# MICRO_SQUARED_SENSING_WITH_DIODES.net
KiCad netlist of a schematic drawn in EAGLE
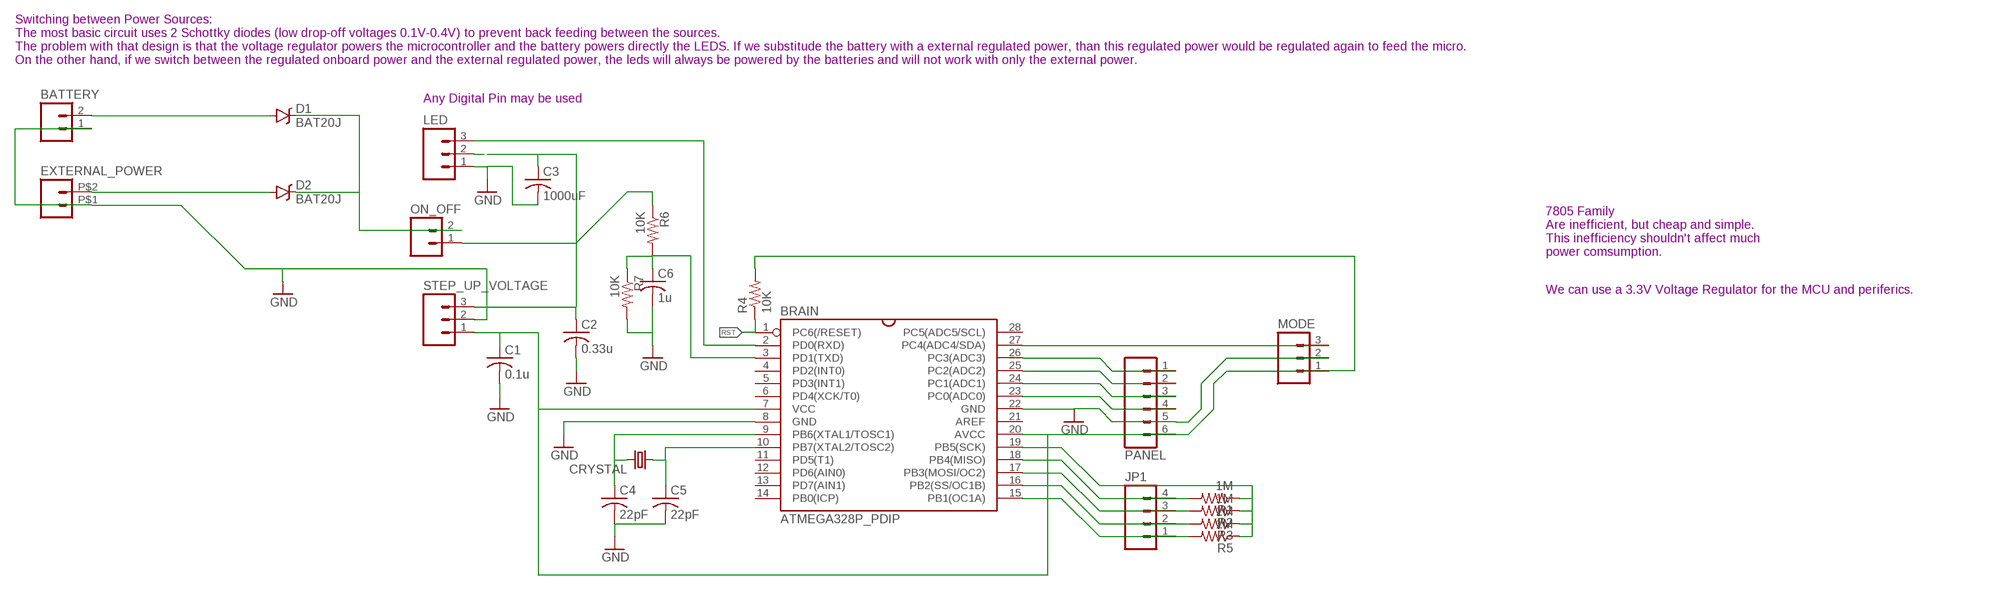
[diagram p0: schematic, sheet 1]

(export (version "E")
  (design (tool "Eeschema 10.0.6"))
  (components
    (comp (ref "BATTERY")
      (value "M02PTH")
      (footprint "eagle-import:1X02")
      (libsource (lib "eagle-import") (part "M02PTH"))
    )
    (comp (ref "BRAIN")
      (value "ATMEGA328P_PDIP")
      (footprint "eagle-import:DIL-28-3")
      (libsource (lib "eagle-import") (part "ATMEGA328P_PDIP"))
    )
    (comp (ref "C1")
      (value "0.1u")
      (footprint "eagle-import:C025-025X050")
      (libsource (lib "eagle-import") (part "C-US025-025X050"))
    )
    (comp (ref "C2")
      (value "0.33u")
      (footprint "eagle-import:C025-025X050")
      (libsource (lib "eagle-import") (part "C-US025-025X050"))
    )
    (comp (ref "C3")
      (value "1000uF")
      (footprint "eagle-import:C050-075X075")
      (libsource (lib "eagle-import") (part "C-US050-075X075"))
    )
    (comp (ref "C4")
      (value "22pF")
      (footprint "eagle-import:C025-024X044")
      (libsource (lib "eagle-import") (part "C-US025-024X044"))
    )
    (comp (ref "C5")
      (value "22pF")
      (footprint "eagle-import:C025-024X044")
      (libsource (lib "eagle-import") (part "C-US025-024X044"))
    )
    (comp (ref "C6")
      (value "1u")
      (footprint "eagle-import:C025-025X050")
      (libsource (lib "eagle-import") (part "C-US025-025X050"))
    )
    (comp (ref "CRYSTAL")
      (value "CRYSTALHC49US")
      (footprint "eagle-import:HC49US")
      (libsource (lib "eagle-import") (part "CRYSTALHC49US"))
    )
    (comp (ref "D1")
      (value "BAT20J")
      (footprint "eagle-import:SOD-323")
      (libsource (lib "eagle-import") (part "DIODE-SCHOTTKY-BAT20J"))
    )
    (comp (ref "D2")
      (value "BAT20J")
      (footprint "eagle-import:SOD-323")
      (libsource (lib "eagle-import") (part "DIODE-SCHOTTKY-BAT20J"))
    )
    (comp (ref "EXTERNAL_POWER")
      (value "M02PTH2")
      (footprint "eagle-import:1X02_BIG")
      (libsource (lib "eagle-import") (part "M02PTH2"))
    )
    (comp (ref "JP1")
      (value "M04PTH")
      (footprint "eagle-import:1X04")
      (libsource (lib "eagle-import") (part "M04PTH"))
    )
    (comp (ref "LED")
      (value "M03PTH")
      (footprint "eagle-import:1X03")
      (libsource (lib "eagle-import") (part "M03PTH"))
    )
    (comp (ref "MODE")
      (value "M03PTH")
      (footprint "eagle-import:1X03")
      (libsource (lib "eagle-import") (part "M03PTH"))
    )
    (comp (ref "ON_OFF")
      (value "M02PTH")
      (footprint "eagle-import:1X02")
      (libsource (lib "eagle-import") (part "M02PTH"))
    )
    (comp (ref "PANEL")
      (value "M06NO_SILK_FEMALE_PTH")
      (footprint "eagle-import:1X06_NO_SILK")
      (libsource (lib "eagle-import") (part "M06NO_SILK_FEMALE_PTH"))
    )
    (comp (ref "R1")
      (value "1M")
      (footprint "eagle-import:AXIAL-0.3")
      (libsource (lib "eagle-import") (part "RESISTORAXIAL-0.3"))
    )
    (comp (ref "R2")
      (value "1M")
      (footprint "eagle-import:AXIAL-0.3")
      (libsource (lib "eagle-import") (part "RESISTORAXIAL-0.3"))
    )
    (comp (ref "R3")
      (value "1M")
      (footprint "eagle-import:AXIAL-0.3")
      (libsource (lib "eagle-import") (part "RESISTORAXIAL-0.3"))
    )
    (comp (ref "R4")
      (value "10K")
      (footprint "eagle-import:AXIAL-0.3")
      (libsource (lib "eagle-import") (part "RESISTORAXIAL-0.3"))
    )
    (comp (ref "R5")
      (value "1M")
      (footprint "eagle-import:AXIAL-0.3")
      (libsource (lib "eagle-import") (part "RESISTORAXIAL-0.3"))
    )
    (comp (ref "R6")
      (value "10K")
      (footprint "eagle-import:AXIAL-0.3")
      (libsource (lib "eagle-import") (part "RESISTORAXIAL-0.3"))
    )
    (comp (ref "R7")
      (value "10K")
      (footprint "eagle-import:AXIAL-0.3")
      (libsource (lib "eagle-import") (part "RESISTORAXIAL-0.3"))
    )
    (comp (ref "STEP_UP_VOLTAGE")
      (value "M03PTH")
      (footprint "eagle-import:1X03")
      (libsource (lib "eagle-import") (part "M03PTH"))
    )
  )
  (nets
    (net (code "1") (name "GND") (class "Default")
      (node (ref "BATTERY") (pin "1") (pinfunction "1_1") (pintype "passive"))
      (node (ref "BRAIN") (pin "22") (pinfunction "GND_22") (pintype "bidirectional"))
      (node (ref "BRAIN") (pin "8") (pinfunction "GND_8") (pintype "bidirectional"))
      (node (ref "C1") (pin "2") (pinfunction "2_2") (pintype "passive"))
      (node (ref "C2") (pin "2") (pinfunction "2_2") (pintype "passive"))
      (node (ref "C3") (pin "2") (pinfunction "2_2") (pintype "passive"))
      (node (ref "C4") (pin "2") (pinfunction "2_2") (pintype "passive"))
      (node (ref "C5") (pin "2") (pinfunction "2_2") (pintype "passive"))
      (node (ref "C6") (pin "2") (pinfunction "2_2") (pintype "passive"))
      (node (ref "EXTERNAL_POWER") (pin "P$1") (pinfunction "1_P$1") (pintype "passive"))
      (node (ref "LED") (pin "1") (pinfunction "1_1") (pintype "passive"))
      (node (ref "MODE") (pin "2") (pinfunction "2_2") (pintype "passive"))
      (node (ref "PANEL") (pin "5") (pinfunction "5_5") (pintype "passive"))
      (node (ref "R7") (pin "P$2") (pinfunction "2_P$2") (pintype "passive"))
      (node (ref "STEP_UP_VOLTAGE") (pin "2") (pinfunction "2_2") (pintype "passive"))
    )
    (net (code "2") (name "Net-(BATTERY-Pad2)") (class "Default")
      (node (ref "BATTERY") (pin "2") (pinfunction "2_2") (pintype "passive"))
      (node (ref "D1") (pin "A") (pinfunction "A_A") (pintype "passive"))
    )
    (net (code "3") (name "Net-(BRAIN-AVCC)") (class "Default")
      (node (ref "BRAIN") (pin "20") (pinfunction "AVCC_20") (pintype "bidirectional"))
      (node (ref "BRAIN") (pin "7") (pinfunction "VCC_7") (pintype "bidirectional"))
      (node (ref "C1") (pin "1") (pinfunction "1_1") (pintype "passive"))
      (node (ref "MODE") (pin "1") (pinfunction "1_1") (pintype "passive"))
      (node (ref "PANEL") (pin "6") (pinfunction "6_6") (pintype "passive"))
      (node (ref "R4") (pin "P$2") (pinfunction "2_P$2") (pintype "passive"))
      (node (ref "STEP_UP_VOLTAGE") (pin "1") (pinfunction "1_1") (pintype "passive"))
    )
    (net (code "4") (name "Net-(BRAIN-PB1(OC1A))") (class "Default")
      (node (ref "BRAIN") (pin "15") (pinfunction "PB1(OC1A)_15") (pintype "bidirectional"))
      (node (ref "JP1") (pin "1") (pinfunction "1_1") (pintype "passive"))
      (node (ref "R5") (pin "P$2") (pinfunction "2_P$2") (pintype "passive"))
    )
    (net (code "5") (name "Net-(BRAIN-PB2(SS{slash}OC1B))") (class "Default")
      (node (ref "BRAIN") (pin "16") (pinfunction "PB2(SS/OC1B)_16") (pintype "bidirectional"))
      (node (ref "JP1") (pin "2") (pinfunction "2_2") (pintype "passive"))
      (node (ref "R3") (pin "P$2") (pinfunction "2_P$2") (pintype "passive"))
    )
    (net (code "6") (name "Net-(BRAIN-PB3(MOSI{slash}OC2))") (class "Default")
      (node (ref "BRAIN") (pin "17") (pinfunction "PB3(MOSI/OC2)_17") (pintype "bidirectional"))
      (node (ref "JP1") (pin "3") (pinfunction "3_3") (pintype "passive"))
      (node (ref "R2") (pin "P$2") (pinfunction "2_P$2") (pintype "passive"))
    )
    (net (code "7") (name "Net-(BRAIN-PB4(MISO))") (class "Default")
      (node (ref "BRAIN") (pin "18") (pinfunction "PB4(MISO)_18") (pintype "bidirectional"))
      (node (ref "JP1") (pin "4") (pinfunction "4_4") (pintype "passive"))
      (node (ref "R1") (pin "P$2") (pinfunction "2_P$2") (pintype "passive"))
    )
    (net (code "8") (name "Net-(BRAIN-PB5(SCK))") (class "Default")
      (node (ref "BRAIN") (pin "19") (pinfunction "PB5(SCK)_19") (pintype "bidirectional"))
      (node (ref "R1") (pin "P$1") (pinfunction "1_P$1") (pintype "passive"))
      (node (ref "R2") (pin "P$1") (pinfunction "1_P$1") (pintype "passive"))
      (node (ref "R3") (pin "P$1") (pinfunction "1_P$1") (pintype "passive"))
      (node (ref "R5") (pin "P$1") (pinfunction "1_P$1") (pintype "passive"))
    )
    (net (code "9") (name "Net-(BRAIN-PB6(XTAL1{slash}TOSC1))") (class "Default")
      (node (ref "BRAIN") (pin "9") (pinfunction "PB6(XTAL1/TOSC1)_9") (pintype "bidirectional"))
      (node (ref "C4") (pin "1") (pinfunction "1_1") (pintype "passive"))
      (node (ref "CRYSTAL") (pin "2") (pinfunction "2_2") (pintype "passive"))
    )
    (net (code "10") (name "Net-(BRAIN-PB7(XTAL2{slash}TOSC2))") (class "Default")
      (node (ref "BRAIN") (pin "10") (pinfunction "PB7(XTAL2/TOSC2)_10") (pintype "bidirectional"))
      (node (ref "C5") (pin "1") (pinfunction "1_1") (pintype "passive"))
      (node (ref "CRYSTAL") (pin "1") (pinfunction "1_1") (pintype "passive"))
    )
    (net (code "11") (name "Net-(BRAIN-PC0(ADC0))") (class "Default")
      (node (ref "BRAIN") (pin "23") (pinfunction "PC0(ADC0)_23") (pintype "bidirectional"))
      (node (ref "PANEL") (pin "4") (pinfunction "4_4") (pintype "passive"))
    )
    (net (code "12") (name "Net-(BRAIN-PC1(ADC1))") (class "Default")
      (node (ref "BRAIN") (pin "24") (pinfunction "PC1(ADC1)_24") (pintype "bidirectional"))
      (node (ref "PANEL") (pin "3") (pinfunction "3_3") (pintype "passive"))
    )
    (net (code "13") (name "Net-(BRAIN-PC2(ADC2))") (class "Default")
      (node (ref "BRAIN") (pin "25") (pinfunction "PC2(ADC2)_25") (pintype "bidirectional"))
      (node (ref "PANEL") (pin "2") (pinfunction "2_2") (pintype "passive"))
    )
    (net (code "14") (name "Net-(BRAIN-PC3(ADC3))") (class "Default")
      (node (ref "BRAIN") (pin "26") (pinfunction "PC3(ADC3)_26") (pintype "bidirectional"))
      (node (ref "PANEL") (pin "1") (pinfunction "1_1") (pintype "passive"))
    )
    (net (code "15") (name "Net-(BRAIN-PC4(ADC4{slash}SDA))") (class "Default")
      (node (ref "BRAIN") (pin "27") (pinfunction "PC4(ADC4/SDA)_27") (pintype "bidirectional"))
      (node (ref "MODE") (pin "3") (pinfunction "3_3") (pintype "passive"))
    )
    (net (code "16") (name "Net-(BRAIN-PD0(RXD))") (class "Default")
      (node (ref "BRAIN") (pin "2") (pinfunction "PD0(RXD)_2") (pintype "bidirectional"))
      (node (ref "LED") (pin "3") (pinfunction "3_3") (pintype "passive"))
    )
    (net (code "17") (name "Net-(BRAIN-PD1(TXD))") (class "Default")
      (node (ref "BRAIN") (pin "3") (pinfunction "PD1(TXD)_3") (pintype "bidirectional"))
      (node (ref "C6") (pin "1") (pinfunction "1_1") (pintype "passive"))
      (node (ref "R6") (pin "P$2") (pinfunction "2_P$2") (pintype "passive"))
      (node (ref "R7") (pin "P$1") (pinfunction "1_P$1") (pintype "passive"))
    )
    (net (code "18") (name "Net-(D1-PadC)") (class "Default")
      (node (ref "D1") (pin "C") (pinfunction "C_C") (pintype "passive"))
      (node (ref "D2") (pin "C") (pinfunction "C_C") (pintype "passive"))
      (node (ref "ON_OFF") (pin "2") (pinfunction "2_2") (pintype "passive"))
    )
    (net (code "19") (name "Net-(EXTERNAL_POWER-2)") (class "Default")
      (node (ref "D2") (pin "A") (pinfunction "A_A") (pintype "passive"))
      (node (ref "EXTERNAL_POWER") (pin "P$2") (pinfunction "2_P$2") (pintype "passive"))
    )
    (net (code "20") (name "Net-(R6-1)") (class "Default")
      (node (ref "C2") (pin "1") (pinfunction "1_1") (pintype "passive"))
      (node (ref "C3") (pin "1") (pinfunction "1_1") (pintype "passive"))
      (node (ref "LED") (pin "2") (pinfunction "2_2") (pintype "passive"))
      (node (ref "ON_OFF") (pin "1") (pinfunction "1_1") (pintype "passive"))
      (node (ref "R6") (pin "P$1") (pinfunction "1_P$1") (pintype "passive"))
      (node (ref "STEP_UP_VOLTAGE") (pin "3") (pinfunction "3_3") (pintype "passive"))
    )
    (net (code "21") (name "RST") (class "Default")
      (node (ref "BRAIN") (pin "1") (pinfunction "PC6(/RESET)_1") (pintype "bidirectional"))
      (node (ref "R4") (pin "P$1") (pinfunction "1_P$1") (pintype "passive"))
    )
    (net (code "22") (name "unconnected-(BRAIN-AREF-Pad21)") (class "Default")
      (node (ref "BRAIN") (pin "21") (pinfunction "AREF_21") (pintype "bidirectional"))
    )
    (net (code "23") (name "unconnected-(BRAIN-PB0(ICP)-Pad14)") (class "Default")
      (node (ref "BRAIN") (pin "14") (pinfunction "PB0(ICP)_14") (pintype "bidirectional"))
    )
    (net (code "24") (name "unconnected-(BRAIN-PC5(ADC5{slash}SCL)-Pad28)") (class "Default")
      (node (ref "BRAIN") (pin "28") (pinfunction "PC5(ADC5/SCL)_28") (pintype "bidirectional"))
    )
    (net (code "25") (name "unconnected-(BRAIN-PD2(INT0)-Pad4)") (class "Default")
      (node (ref "BRAIN") (pin "4") (pinfunction "PD2(INT0)_4") (pintype "bidirectional"))
    )
    (net (code "26") (name "unconnected-(BRAIN-PD3(INT1)-Pad5)") (class "Default")
      (node (ref "BRAIN") (pin "5") (pinfunction "PD3(INT1)_5") (pintype "bidirectional"))
    )
    (net (code "27") (name "unconnected-(BRAIN-PD4(XCK{slash}T0)-Pad6)") (class "Default")
      (node (ref "BRAIN") (pin "6") (pinfunction "PD4(XCK/T0)_6") (pintype "bidirectional"))
    )
    (net (code "28") (name "unconnected-(BRAIN-PD5(T1)-Pad11)") (class "Default")
      (node (ref "BRAIN") (pin "11") (pinfunction "PD5(T1)_11") (pintype "bidirectional"))
    )
    (net (code "29") (name "unconnected-(BRAIN-PD6(AIN0)-Pad12)") (class "Default")
      (node (ref "BRAIN") (pin "12") (pinfunction "PD6(AIN0)_12") (pintype "bidirectional"))
    )
    (net (code "30") (name "unconnected-(BRAIN-PD7(AIN1)-Pad13)") (class "Default")
      (node (ref "BRAIN") (pin "13") (pinfunction "PD7(AIN1)_13") (pintype "bidirectional"))
    )
  )
)
